# VolumeKnob.net
KiCad netlist of a schematic drawn in EAGLE
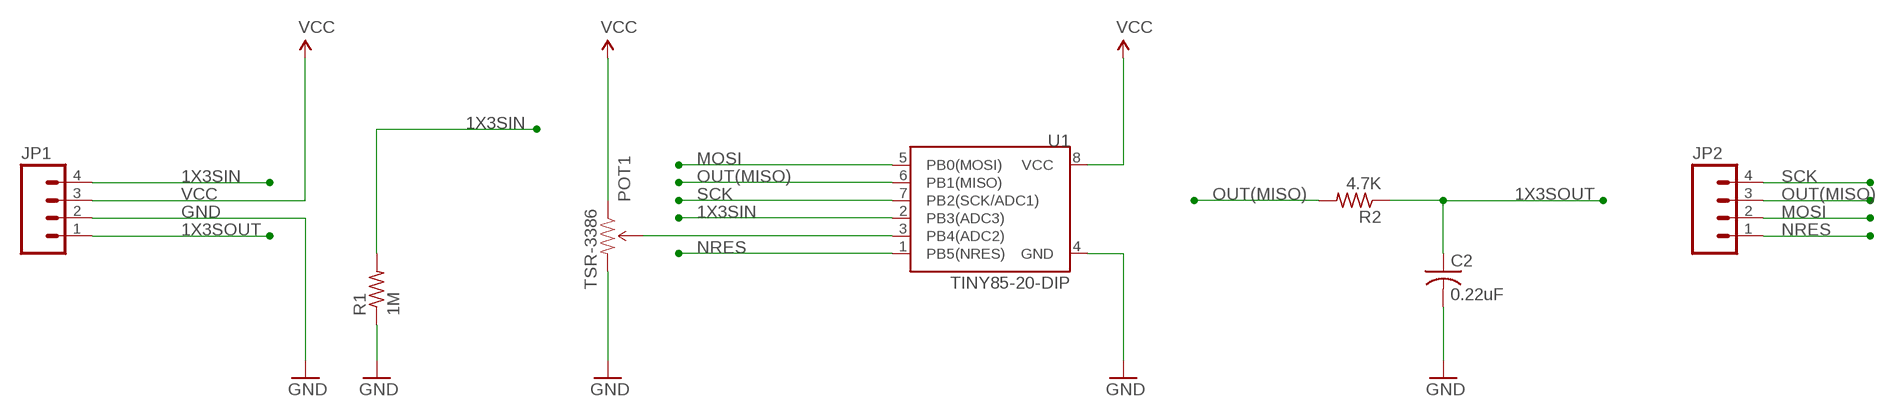
[diagram p0: schematic, sheet 1]

(export (version "E")
  (design (tool "Eeschema 10.0.6"))
  (components
    (comp (ref "C2")
      (value "0.22uF")
      (footprint "eagle-import:C0603")
      (libsource (lib "eagle-import") (part "C-USC0603"))
    )
    (comp (ref "JP1")
      (value "M04PTH")
      (footprint "eagle-import:1X04")
      (libsource (lib "eagle-import") (part "M04PTH"))
    )
    (comp (ref "JP2")
      (value "M04PTH")
      (footprint "eagle-import:1X04")
      (libsource (lib "eagle-import") (part "M04PTH"))
    )
    (comp (ref "POT1")
      (value "TSR-3386")
      (footprint "eagle-import:3386U")
      (libsource (lib "eagle-import") (part "TRIMPOT-PTH-KNOB"))
    )
    (comp (ref "R1")
      (value "1M")
      (footprint "eagle-import:R0603")
      (libsource (lib "eagle-import") (part "R-US_R0603"))
    )
    (comp (ref "R2")
      (value "4.7K")
      (footprint "eagle-import:R0603")
      (libsource (lib "eagle-import") (part "R-US_R0603"))
    )
    (comp (ref "U1")
      (value "TINY85-20-DIP")
      (footprint "eagle-import:DIP08")
      (libsource (lib "eagle-import") (part "ATTINY45TINY85-20-DIP"))
    )
  )
  (nets
    (net (code "1") (name "/1X3SIN") (class "Default")
      (node (ref "JP1") (pin "4") (pinfunction "4_4") (pintype "passive"))
      (node (ref "R1") (pin "2") (pinfunction "2_2") (pintype "passive"))
      (node (ref "U1") (pin "2") (pinfunction "PB3(ADC3)_2") (pintype "bidirectional"))
    )
    (net (code "2") (name "/1X3SOUT") (class "Default")
      (node (ref "C2") (pin "1") (pinfunction "1_1") (pintype "passive"))
      (node (ref "JP1") (pin "1") (pinfunction "1_1") (pintype "passive"))
      (node (ref "R2") (pin "1") (pinfunction "1_1") (pintype "passive"))
    )
    (net (code "3") (name "/MOSI") (class "Default")
      (node (ref "JP2") (pin "2") (pinfunction "2_2") (pintype "passive"))
      (node (ref "U1") (pin "5") (pinfunction "PB0(MOSI)_5") (pintype "bidirectional"))
    )
    (net (code "4") (name "/NRES") (class "Default")
      (node (ref "JP2") (pin "1") (pinfunction "1_1") (pintype "passive"))
      (node (ref "U1") (pin "1") (pinfunction "PB5(NRES)_1") (pintype "bidirectional"))
    )
    (net (code "5") (name "/OUT(MISO)") (class "Default")
      (node (ref "JP2") (pin "3") (pinfunction "3_3") (pintype "passive"))
      (node (ref "R2") (pin "2") (pinfunction "2_2") (pintype "passive"))
      (node (ref "U1") (pin "6") (pinfunction "PB1(MISO)_6") (pintype "bidirectional"))
    )
    (net (code "6") (name "/SCK") (class "Default")
      (node (ref "JP2") (pin "4") (pinfunction "4_4") (pintype "passive"))
      (node (ref "U1") (pin "7") (pinfunction "PB2(SCK/ADC1)_7") (pintype "bidirectional"))
    )
    (net (code "7") (name "GND") (class "Default")
      (node (ref "C2") (pin "2") (pinfunction "2_2") (pintype "passive"))
      (node (ref "JP1") (pin "2") (pinfunction "2_2") (pintype "passive"))
      (node (ref "POT1") (pin "3") (pinfunction "CW_3") (pintype "passive"))
      (node (ref "R1") (pin "1") (pinfunction "1_1") (pintype "passive"))
      (node (ref "U1") (pin "4") (pinfunction "GND_4") (pintype "bidirectional"))
    )
    (net (code "8") (name "Net-(POT1-WIPER)") (class "Default")
      (node (ref "POT1") (pin "2") (pinfunction "WIPER_2") (pintype "passive"))
      (node (ref "U1") (pin "3") (pinfunction "PB4(ADC2)_3") (pintype "bidirectional"))
    )
    (net (code "9") (name "VCC") (class "Default")
      (node (ref "JP1") (pin "3") (pinfunction "3_3") (pintype "passive"))
      (node (ref "POT1") (pin "1") (pinfunction "CCW_1") (pintype "passive"))
      (node (ref "U1") (pin "8") (pinfunction "VCC_8") (pintype "bidirectional"))
    )
  )
)
